# Indication.net
KiCad netlist of a schematic drawn in Altium Designer
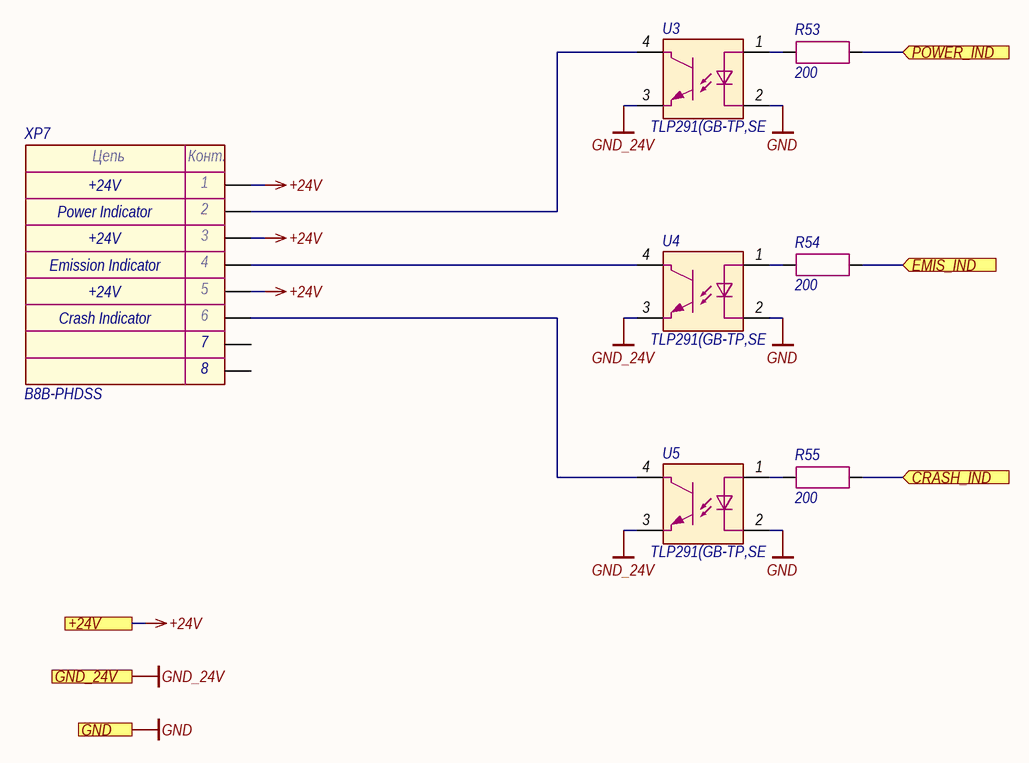
[diagram p0: Indication.SchDoc]

(export (version "E")
  (design (tool "Eeschema 10.0.6"))
  (components
    (comp (ref "R53")
      (value "200")
      (footprint "Pcb_library:RES_0603")
      (fields (field (name "MANUFACTURER") "Yageo"))
      (libsource (lib "Schem_library") (part "Resistor"))
    )
    (comp (ref "R54")
      (value "200")
      (footprint "Pcb_library:RES_0603")
      (fields (field (name "MANUFACTURER") "Yageo"))
      (libsource (lib "Schem_library") (part "Resistor"))
    )
    (comp (ref "R55")
      (value "200")
      (footprint "Pcb_library:RES_0603")
      (fields (field (name "MANUFACTURER") "Yageo"))
      (libsource (lib "Schem_library") (part "Resistor"))
    )
    (comp (ref "U3")
      (value "TLP291(GB-TP,SE")
      (footprint "Pcb_library:11-3C1")
      (fields (field (name "MANUFACTURER") "Toshiba"))
      (libsource (lib "Schem_library") (part "TLP291"))
    )
    (comp (ref "U4")
      (value "TLP291(GB-TP,SE")
      (footprint "Pcb_library:11-3C1")
      (fields (field (name "MANUFACTURER") "Toshiba"))
      (libsource (lib "Schem_library") (part "TLP291"))
    )
    (comp (ref "U5")
      (value "TLP291(GB-TP,SE")
      (footprint "Pcb_library:11-3C1")
      (fields (field (name "MANUFACTURER") "Toshiba"))
      (libsource (lib "Schem_library") (part "TLP291"))
    )
    (comp (ref "XP7")
      (value "B8B-PHDSS")
      (footprint "Pcb_library:B8B-PHDSS")
      (fields (field (name "MANUFACTURER") "JST"))
      (libsource (lib "Schem_library") (part "Connector-8"))
    )
  )
  (nets
    (net (code "1") (name "+24V") (class "Default")
      (node (ref "XP7") (pin "1") (pintype "passive"))
      (node (ref "XP7") (pin "3") (pintype "passive"))
      (node (ref "XP7") (pin "5") (pintype "passive"))
    )
    (net (code "2") (name "/CRASH_IND") (class "Default")
      (node (ref "R55") (pin "2") (pinfunction "2_2") (pintype "passive"))
    )
    (net (code "3") (name "/EMIS_IND") (class "Default")
      (node (ref "R54") (pin "2") (pinfunction "2_2") (pintype "passive"))
    )
    (net (code "4") (name "/POWER_IND") (class "Default")
      (node (ref "R53") (pin "2") (pinfunction "2_2") (pintype "passive"))
    )
    (net (code "5") (name "GND") (class "Default")
      (node (ref "U3") (pin "2") (pintype "passive"))
      (node (ref "U4") (pin "2") (pintype "passive"))
      (node (ref "U5") (pin "2") (pintype "passive"))
    )
    (net (code "6") (name "GND_24V") (class "Default")
      (node (ref "U3") (pin "3") (pintype "passive"))
      (node (ref "U4") (pin "3") (pintype "passive"))
      (node (ref "U5") (pin "3") (pintype "passive"))
    )
    (net (code "7") (name "Net-(R53-Pad1)") (class "Default")
      (node (ref "R53") (pin "1") (pinfunction "1_1") (pintype "passive"))
      (node (ref "U3") (pin "1") (pintype "passive"))
    )
    (net (code "8") (name "Net-(R54-Pad1)") (class "Default")
      (node (ref "R54") (pin "1") (pinfunction "1_1") (pintype "passive"))
      (node (ref "U4") (pin "1") (pintype "passive"))
    )
    (net (code "9") (name "Net-(R55-Pad1)") (class "Default")
      (node (ref "R55") (pin "1") (pinfunction "1_1") (pintype "passive"))
      (node (ref "U5") (pin "1") (pintype "passive"))
    )
    (net (code "10") (name "Net-(U3-Pad4)") (class "Default")
      (node (ref "U3") (pin "4") (pintype "passive"))
      (node (ref "XP7") (pin "2") (pintype "passive"))
    )
    (net (code "11") (name "Net-(U4-Pad4)") (class "Default")
      (node (ref "U4") (pin "4") (pintype "passive"))
      (node (ref "XP7") (pin "4") (pintype "passive"))
    )
    (net (code "12") (name "Net-(U5-Pad4)") (class "Default")
      (node (ref "U5") (pin "4") (pintype "passive"))
      (node (ref "XP7") (pin "6") (pintype "passive"))
    )
    (net (code "13") (name "unconnected-(XP7-Pad7)") (class "Default")
      (node (ref "XP7") (pin "7") (pintype "passive"))
    )
    (net (code "14") (name "unconnected-(XP7-Pad8)") (class "Default")
      (node (ref "XP7") (pin "8") (pintype "passive"))
    )
  )
)
